# genericNode.net
KiCad netlist of a schematic drawn in EAGLE
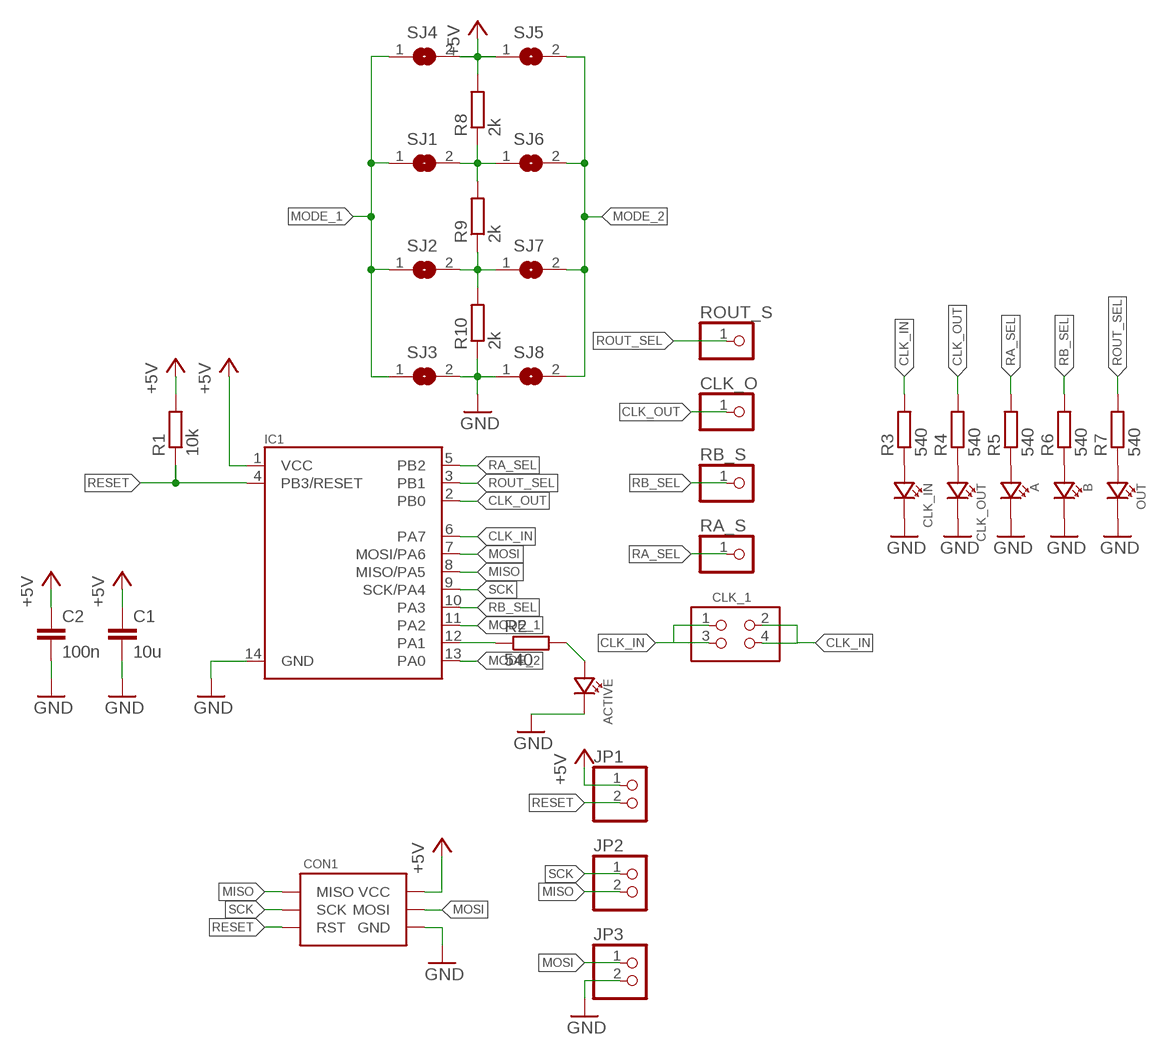
[diagram p0: schematic, sheet 1]

(export (version "E")
  (design (tool "Eeschema 10.0.6"))
  (components
    (comp (ref "A")
      (value "LED0805")
      (footprint "eagle-import:CHIPLED_0805")
      (libsource (lib "eagle-import") (part "LED0805"))
    )
    (comp (ref "ACTIVE")
      (value "LED0805")
      (footprint "eagle-import:CHIPLED_0805")
      (libsource (lib "eagle-import") (part "LED0805"))
    )
    (comp (ref "B")
      (value "LED0805")
      (footprint "eagle-import:CHIPLED_0805")
      (libsource (lib "eagle-import") (part "LED0805"))
    )
    (comp (ref "C1")
      (value "10u")
      (footprint "eagle-import:C0805")
      (libsource (lib "eagle-import") (part "C-EUC0805"))
    )
    (comp (ref "C2")
      (value "100n")
      (footprint "eagle-import:C0603")
      (libsource (lib "eagle-import") (part "C-EUC0603"))
    )
    (comp (ref "CLK_1")
      (value "GENERIC-2X2-EDGE")
      (footprint "eagle-import:PINHEADER-100MIL-2X2-EDGE")
      (libsource (lib "eagle-import") (part "GENERIC-2X2-EDGE"))
    )
    (comp (ref "CLK_IN")
      (value "LED0805")
      (footprint "eagle-import:CHIPLED_0805")
      (libsource (lib "eagle-import") (part "LED0805"))
    )
    (comp (ref "CLK_O")
      (value "PINHD-1X1")
      (footprint "eagle-import:1X01")
      (libsource (lib "eagle-import") (part "PINHD-1X1"))
    )
    (comp (ref "CLK_OUT")
      (value "LED0805")
      (footprint "eagle-import:CHIPLED_0805")
      (libsource (lib "eagle-import") (part "LED0805"))
    )
    (comp (ref "CON1")
      (value "ISP-6_PIN-POGO")
      (footprint "eagle-import:POGO-1.27-6_PIN-MADWORM")
      (libsource (lib "eagle-import") (part "ISP-6_PIN-POGO"))
    )
    (comp (ref "IC1")
      (value "AVR-ATTINY24/44/84-SOIC14")
      (footprint "eagle-import:SOIC14")
      (libsource (lib "eagle-import") (part "AVR-ATTINY24/44/84-SOIC14"))
    )
    (comp (ref "JP1")
      (value "PINHD-1X2")
      (footprint "eagle-import:1X02")
      (libsource (lib "eagle-import") (part "PINHD-1X2"))
    )
    (comp (ref "JP2")
      (value "PINHD-1X2")
      (footprint "eagle-import:1X02")
      (libsource (lib "eagle-import") (part "PINHD-1X2"))
    )
    (comp (ref "JP3")
      (value "PINHD-1X2")
      (footprint "eagle-import:1X02")
      (libsource (lib "eagle-import") (part "PINHD-1X2"))
    )
    (comp (ref "OUT")
      (value "LED0805")
      (footprint "eagle-import:CHIPLED_0805")
      (libsource (lib "eagle-import") (part "LED0805"))
    )
    (comp (ref "R1")
      (value "10k")
      (footprint "eagle-import:R0603")
      (libsource (lib "eagle-import") (part "R-EU_R0603"))
    )
    (comp (ref "R2")
      (value "540")
      (footprint "eagle-import:R0603")
      (libsource (lib "eagle-import") (part "R-EU_R0603"))
    )
    (comp (ref "R3")
      (value "540")
      (footprint "eagle-import:R0603")
      (libsource (lib "eagle-import") (part "R-EU_R0603"))
    )
    (comp (ref "R4")
      (value "540")
      (footprint "eagle-import:R0603")
      (libsource (lib "eagle-import") (part "R-EU_R0603"))
    )
    (comp (ref "R5")
      (value "540")
      (footprint "eagle-import:R0603")
      (libsource (lib "eagle-import") (part "R-EU_R0603"))
    )
    (comp (ref "R6")
      (value "540")
      (footprint "eagle-import:R0603")
      (libsource (lib "eagle-import") (part "R-EU_R0603"))
    )
    (comp (ref "R7")
      (value "540")
      (footprint "eagle-import:R0603")
      (libsource (lib "eagle-import") (part "R-EU_R0603"))
    )
    (comp (ref "R8")
      (value "2k")
      (footprint "eagle-import:R0603")
      (libsource (lib "eagle-import") (part "R-EU_R0603"))
    )
    (comp (ref "R9")
      (value "2k")
      (footprint "eagle-import:R0603")
      (libsource (lib "eagle-import") (part "R-EU_R0603"))
    )
    (comp (ref "R10")
      (value "2k")
      (footprint "eagle-import:R0603")
      (libsource (lib "eagle-import") (part "R-EU_R0603"))
    )
    (comp (ref "RA_S")
      (value "PINHD-1X1")
      (footprint "eagle-import:1X01")
      (libsource (lib "eagle-import") (part "PINHD-1X1"))
    )
    (comp (ref "RB_S")
      (value "PINHD-1X1")
      (footprint "eagle-import:1X01")
      (libsource (lib "eagle-import") (part "PINHD-1X1"))
    )
    (comp (ref "ROUT_S")
      (value "PINHD-1X1")
      (footprint "eagle-import:1X01")
      (libsource (lib "eagle-import") (part "PINHD-1X1"))
    )
    (comp (ref "SJ1") (value "SJ") (footprint "eagle-import:SJ") (libsource (lib "eagle-import") (part "SJ")))
    (comp (ref "SJ2") (value "SJ") (footprint "eagle-import:SJ") (libsource (lib "eagle-import") (part "SJ")))
    (comp (ref "SJ3") (value "SJ") (footprint "eagle-import:SJ") (libsource (lib "eagle-import") (part "SJ")))
    (comp (ref "SJ4") (value "SJ") (footprint "eagle-import:SJ") (libsource (lib "eagle-import") (part "SJ")))
    (comp (ref "SJ5") (value "SJ") (footprint "eagle-import:SJ") (libsource (lib "eagle-import") (part "SJ")))
    (comp (ref "SJ6") (value "SJ") (footprint "eagle-import:SJ") (libsource (lib "eagle-import") (part "SJ")))
    (comp (ref "SJ7") (value "SJ") (footprint "eagle-import:SJ") (libsource (lib "eagle-import") (part "SJ")))
    (comp (ref "SJ8") (value "SJ") (footprint "eagle-import:SJ") (libsource (lib "eagle-import") (part "SJ")))
  )
  (nets
    (net (code "1") (name "+5V") (class "Default")
      (node (ref "C1") (pin "1") (pinfunction "1_1") (pintype "passive"))
      (node (ref "C2") (pin "1") (pinfunction "1_1") (pintype "passive"))
      (node (ref "CON1") (pin "P$2") (pinfunction "VCC_P$2") (pintype "power_in"))
      (node (ref "IC1") (pin "1") (pinfunction "VCC_1") (pintype "bidirectional"))
      (node (ref "JP1") (pin "1") (pinfunction "1_1") (pintype "passive"))
      (node (ref "R1") (pin "2") (pinfunction "2_2") (pintype "passive"))
      (node (ref "R8") (pin "2") (pinfunction "2_2") (pintype "passive"))
      (node (ref "SJ4") (pin "2") (pinfunction "2_2") (pintype "passive"))
      (node (ref "SJ5") (pin "1") (pinfunction "1_1") (pintype "passive"))
    )
    (net (code "2") (name "CLK_IN") (class "Default")
      (node (ref "CLK_1") (pin "1") (pinfunction "1_1") (pintype "bidirectional"))
      (node (ref "CLK_1") (pin "2") (pinfunction "2_2") (pintype "bidirectional"))
      (node (ref "CLK_1") (pin "3") (pinfunction "3_3") (pintype "bidirectional"))
      (node (ref "CLK_1") (pin "4") (pinfunction "4_4") (pintype "bidirectional"))
      (node (ref "IC1") (pin "6") (pinfunction "PA7_6") (pintype "bidirectional"))
      (node (ref "R3") (pin "2") (pinfunction "2_2") (pintype "passive"))
    )
    (net (code "3") (name "CLK_OUT") (class "Default")
      (node (ref "CLK_O") (pin "1") (pinfunction "1_1") (pintype "passive"))
      (node (ref "IC1") (pin "2") (pinfunction "PB0_2") (pintype "bidirectional"))
      (node (ref "R4") (pin "2") (pinfunction "2_2") (pintype "passive"))
    )
    (net (code "4") (name "GND") (class "Default")
      (node (ref "A") (pin "C") (pinfunction "C_C") (pintype "bidirectional"))
      (node (ref "ACTIVE") (pin "C") (pinfunction "C_C") (pintype "bidirectional"))
      (node (ref "B") (pin "C") (pinfunction "C_C") (pintype "bidirectional"))
      (node (ref "C1") (pin "2") (pinfunction "2_2") (pintype "passive"))
      (node (ref "C2") (pin "2") (pinfunction "2_2") (pintype "passive"))
      (node (ref "CLK_IN") (pin "C") (pinfunction "C_C") (pintype "bidirectional"))
      (node (ref "CLK_OUT") (pin "C") (pinfunction "C_C") (pintype "bidirectional"))
      (node (ref "CON1") (pin "P$6") (pinfunction "GND_P$6") (pintype "power_in"))
      (node (ref "IC1") (pin "14") (pinfunction "GND_14") (pintype "bidirectional"))
      (node (ref "JP3") (pin "2") (pinfunction "2_2") (pintype "passive"))
      (node (ref "OUT") (pin "C") (pinfunction "C_C") (pintype "bidirectional"))
      (node (ref "R10") (pin "1") (pinfunction "1_1") (pintype "passive"))
      (node (ref "SJ3") (pin "2") (pinfunction "2_2") (pintype "passive"))
      (node (ref "SJ8") (pin "1") (pinfunction "1_1") (pintype "passive"))
    )
    (net (code "5") (name "MISO") (class "Default")
      (node (ref "CON1") (pin "P$1") (pinfunction "MISO_P$1") (pintype "bidirectional"))
      (node (ref "IC1") (pin "8") (pinfunction "MISO/PA5_8") (pintype "bidirectional"))
      (node (ref "JP2") (pin "2") (pinfunction "2_2") (pintype "passive"))
    )
    (net (code "6") (name "MODE_1") (class "Default")
      (node (ref "IC1") (pin "11") (pinfunction "PA2_11") (pintype "bidirectional"))
      (node (ref "SJ1") (pin "1") (pinfunction "1_1") (pintype "passive"))
      (node (ref "SJ2") (pin "1") (pinfunction "1_1") (pintype "passive"))
      (node (ref "SJ3") (pin "1") (pinfunction "1_1") (pintype "passive"))
      (node (ref "SJ4") (pin "1") (pinfunction "1_1") (pintype "passive"))
    )
    (net (code "7") (name "MODE_2") (class "Default")
      (node (ref "IC1") (pin "13") (pinfunction "PA0_13") (pintype "bidirectional"))
      (node (ref "SJ5") (pin "2") (pinfunction "2_2") (pintype "passive"))
      (node (ref "SJ6") (pin "2") (pinfunction "2_2") (pintype "passive"))
      (node (ref "SJ7") (pin "2") (pinfunction "2_2") (pintype "passive"))
      (node (ref "SJ8") (pin "2") (pinfunction "2_2") (pintype "passive"))
    )
    (net (code "8") (name "MOSI") (class "Default")
      (node (ref "CON1") (pin "P$4") (pinfunction "MOSI_P$4") (pintype "bidirectional"))
      (node (ref "IC1") (pin "7") (pinfunction "MOSI/PA6_7") (pintype "bidirectional"))
      (node (ref "JP3") (pin "1") (pinfunction "1_1") (pintype "passive"))
    )
    (net (code "9") (name "Net-(A-PadA)") (class "Default")
      (node (ref "A") (pin "A") (pinfunction "A_A") (pintype "bidirectional"))
      (node (ref "R5") (pin "1") (pinfunction "1_1") (pintype "passive"))
    )
    (net (code "10") (name "Net-(ACTIVE-PadA)") (class "Default")
      (node (ref "ACTIVE") (pin "A") (pinfunction "A_A") (pintype "bidirectional"))
      (node (ref "R2") (pin "2") (pinfunction "2_2") (pintype "passive"))
    )
    (net (code "11") (name "Net-(B-PadA)") (class "Default")
      (node (ref "B") (pin "A") (pinfunction "A_A") (pintype "bidirectional"))
      (node (ref "R6") (pin "1") (pinfunction "1_1") (pintype "passive"))
    )
    (net (code "12") (name "Net-(CLK_IN-PadA)") (class "Default")
      (node (ref "CLK_IN") (pin "A") (pinfunction "A_A") (pintype "bidirectional"))
      (node (ref "R3") (pin "1") (pinfunction "1_1") (pintype "passive"))
    )
    (net (code "13") (name "Net-(CLK_OUT-PadA)") (class "Default")
      (node (ref "CLK_OUT") (pin "A") (pinfunction "A_A") (pintype "bidirectional"))
      (node (ref "R4") (pin "1") (pinfunction "1_1") (pintype "passive"))
    )
    (net (code "14") (name "Net-(IC1-PA1)") (class "Default")
      (node (ref "IC1") (pin "12") (pinfunction "PA1_12") (pintype "bidirectional"))
      (node (ref "R2") (pin "1") (pinfunction "1_1") (pintype "passive"))
    )
    (net (code "15") (name "Net-(OUT-PadA)") (class "Default")
      (node (ref "OUT") (pin "A") (pinfunction "A_A") (pintype "bidirectional"))
      (node (ref "R7") (pin "1") (pinfunction "1_1") (pintype "passive"))
    )
    (net (code "16") (name "Net-(R8-Pad1)") (class "Default")
      (node (ref "R8") (pin "1") (pinfunction "1_1") (pintype "passive"))
      (node (ref "R9") (pin "2") (pinfunction "2_2") (pintype "passive"))
      (node (ref "SJ1") (pin "2") (pinfunction "2_2") (pintype "passive"))
      (node (ref "SJ6") (pin "1") (pinfunction "1_1") (pintype "passive"))
    )
    (net (code "17") (name "Net-(R10-Pad2)") (class "Default")
      (node (ref "R10") (pin "2") (pinfunction "2_2") (pintype "passive"))
      (node (ref "R9") (pin "1") (pinfunction "1_1") (pintype "passive"))
      (node (ref "SJ2") (pin "2") (pinfunction "2_2") (pintype "passive"))
      (node (ref "SJ7") (pin "1") (pinfunction "1_1") (pintype "passive"))
    )
    (net (code "18") (name "RA_SEL") (class "Default")
      (node (ref "IC1") (pin "5") (pinfunction "PB2_5") (pintype "bidirectional"))
      (node (ref "R5") (pin "2") (pinfunction "2_2") (pintype "passive"))
      (node (ref "RA_S") (pin "1") (pinfunction "1_1") (pintype "passive"))
    )
    (net (code "19") (name "RB_SEL") (class "Default")
      (node (ref "IC1") (pin "10") (pinfunction "PA3_10") (pintype "bidirectional"))
      (node (ref "R6") (pin "2") (pinfunction "2_2") (pintype "passive"))
      (node (ref "RB_S") (pin "1") (pinfunction "1_1") (pintype "passive"))
    )
    (net (code "20") (name "RESET") (class "Default")
      (node (ref "CON1") (pin "P$5") (pinfunction "RST_P$5") (pintype "bidirectional"))
      (node (ref "IC1") (pin "4") (pinfunction "PB3/RESET_4") (pintype "bidirectional"))
      (node (ref "JP1") (pin "2") (pinfunction "2_2") (pintype "passive"))
      (node (ref "R1") (pin "1") (pinfunction "1_1") (pintype "passive"))
    )
    (net (code "21") (name "ROUT_SEL") (class "Default")
      (node (ref "IC1") (pin "3") (pinfunction "PB1_3") (pintype "bidirectional"))
      (node (ref "R7") (pin "2") (pinfunction "2_2") (pintype "passive"))
      (node (ref "ROUT_S") (pin "1") (pinfunction "1_1") (pintype "passive"))
    )
    (net (code "22") (name "SCK") (class "Default")
      (node (ref "CON1") (pin "P$3") (pinfunction "SCK_P$3") (pintype "bidirectional"))
      (node (ref "IC1") (pin "9") (pinfunction "SCK/PA4_9") (pintype "bidirectional"))
      (node (ref "JP2") (pin "1") (pinfunction "1_1") (pintype "passive"))
    )
  )
)
